# benjolin_1_6.net
KiCad netlist of a schematic drawn in EAGLE
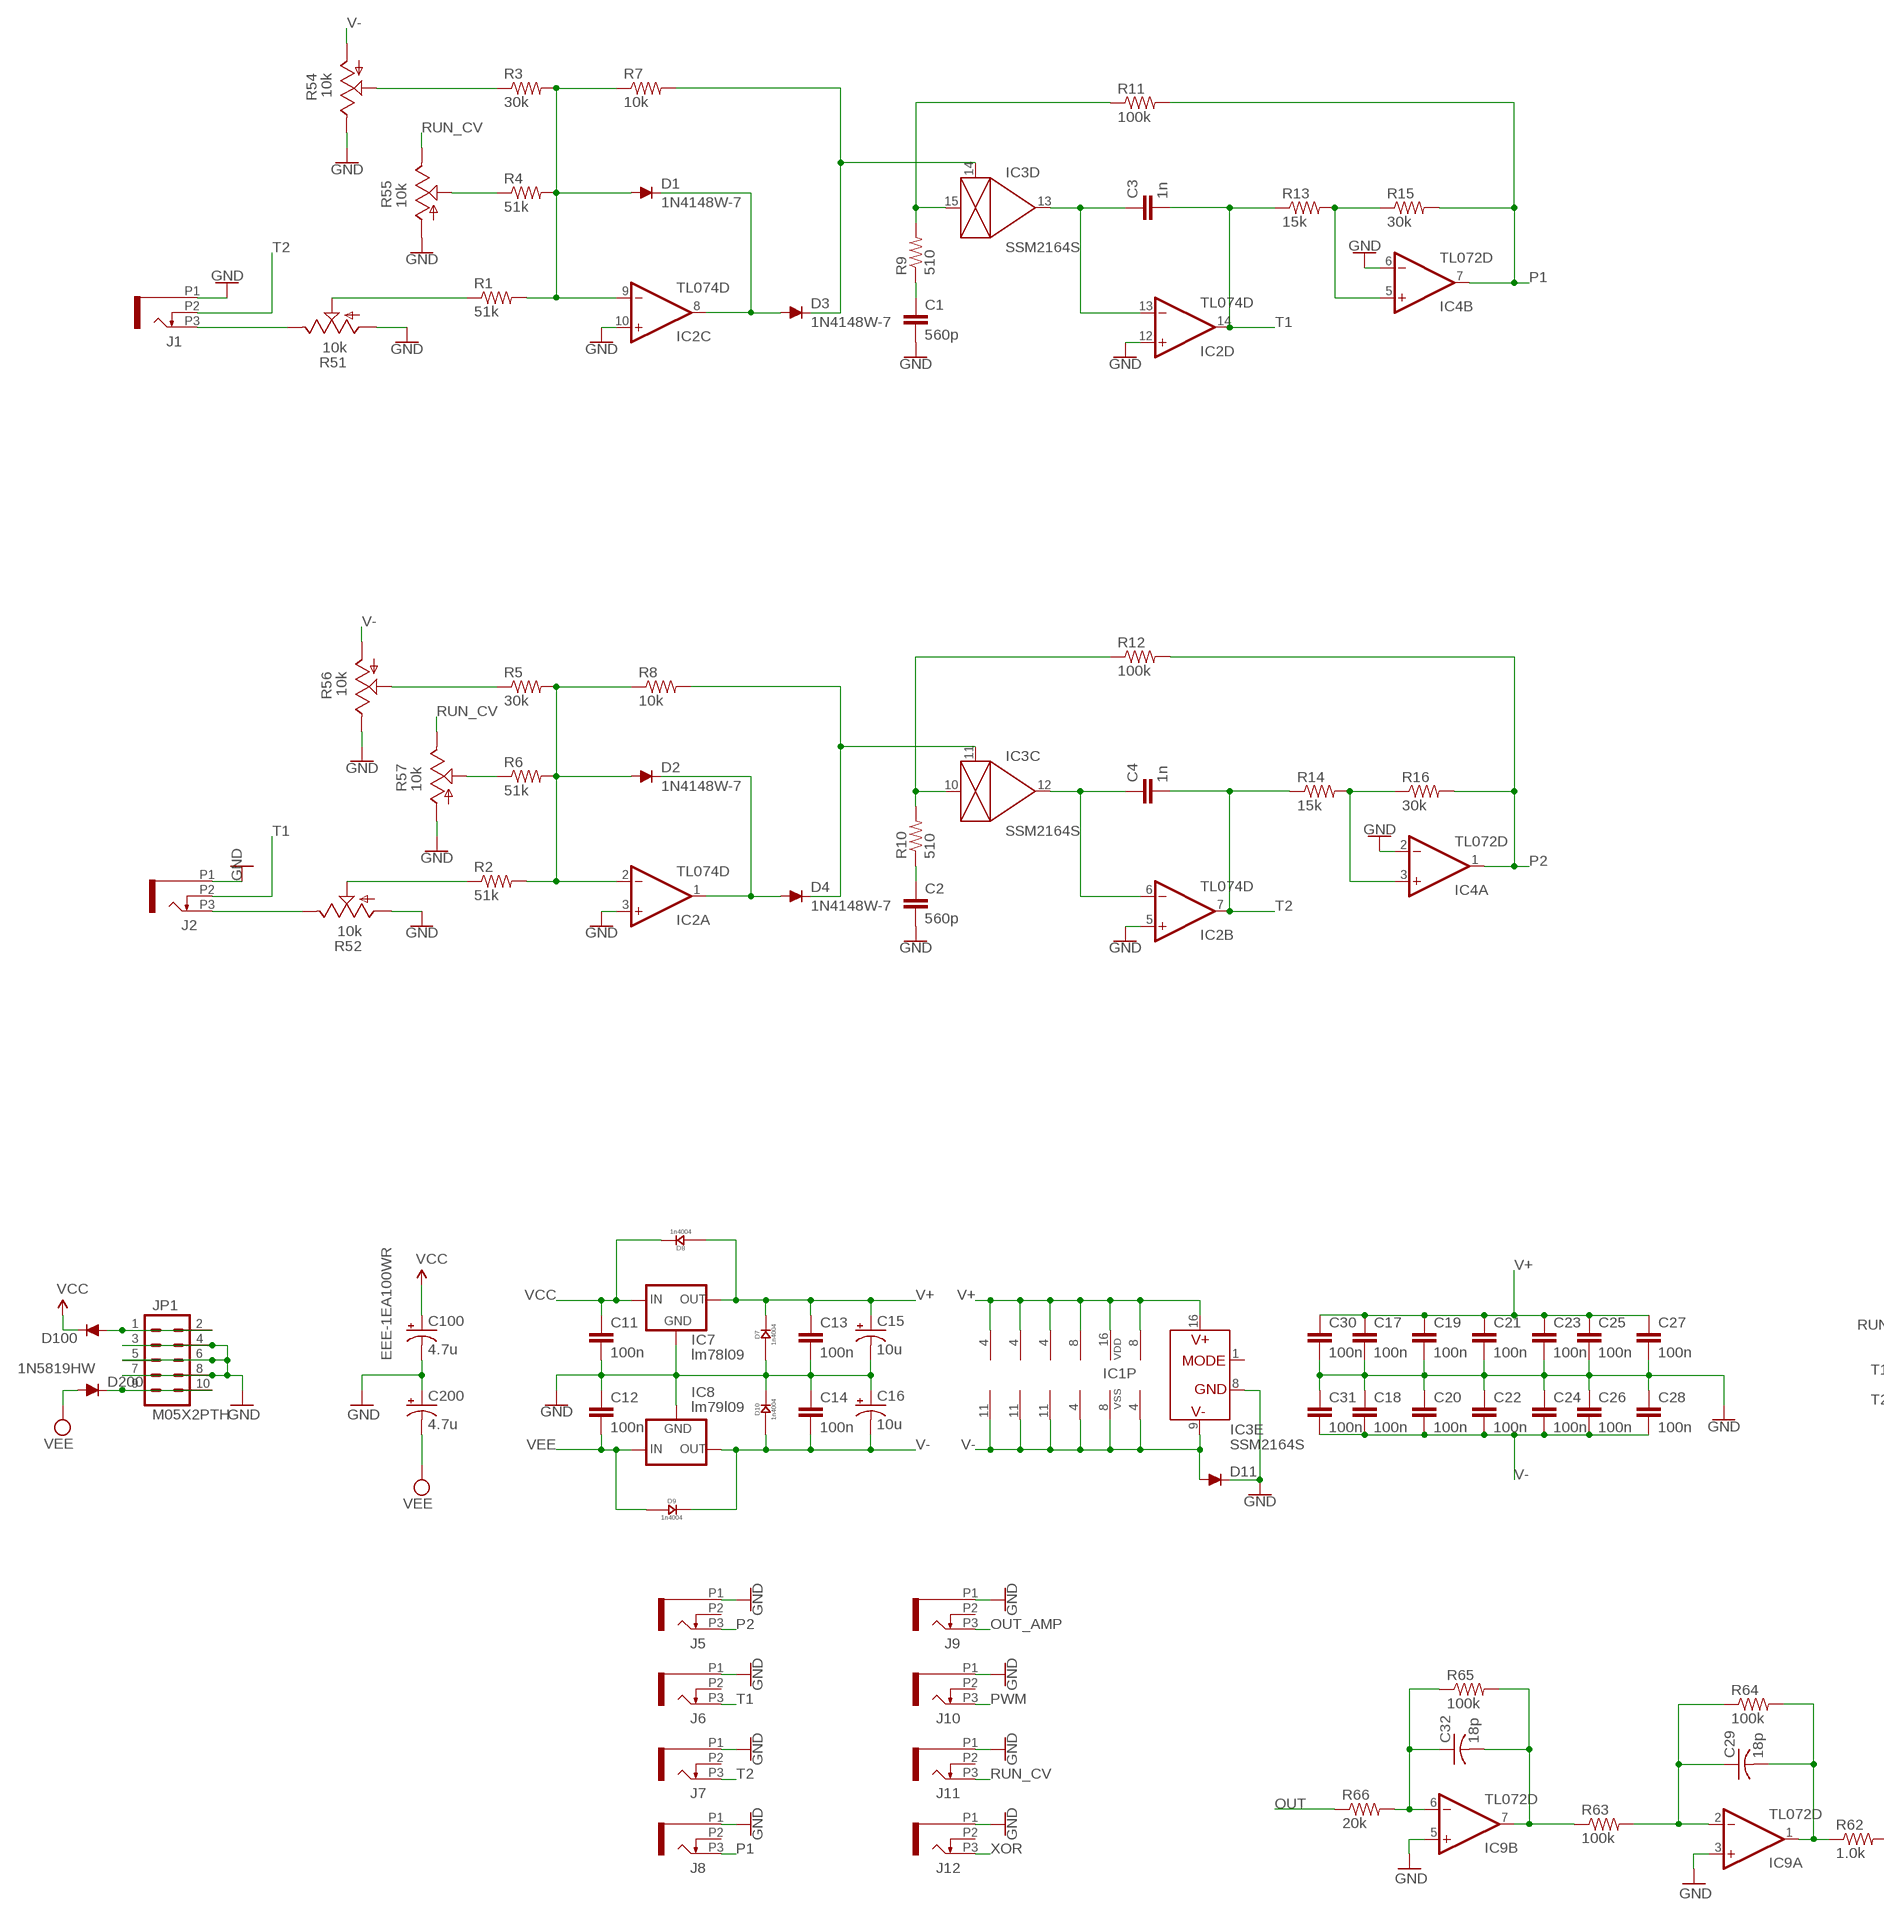
[diagram p0: schematic, sheet 1, part 1 of 2]
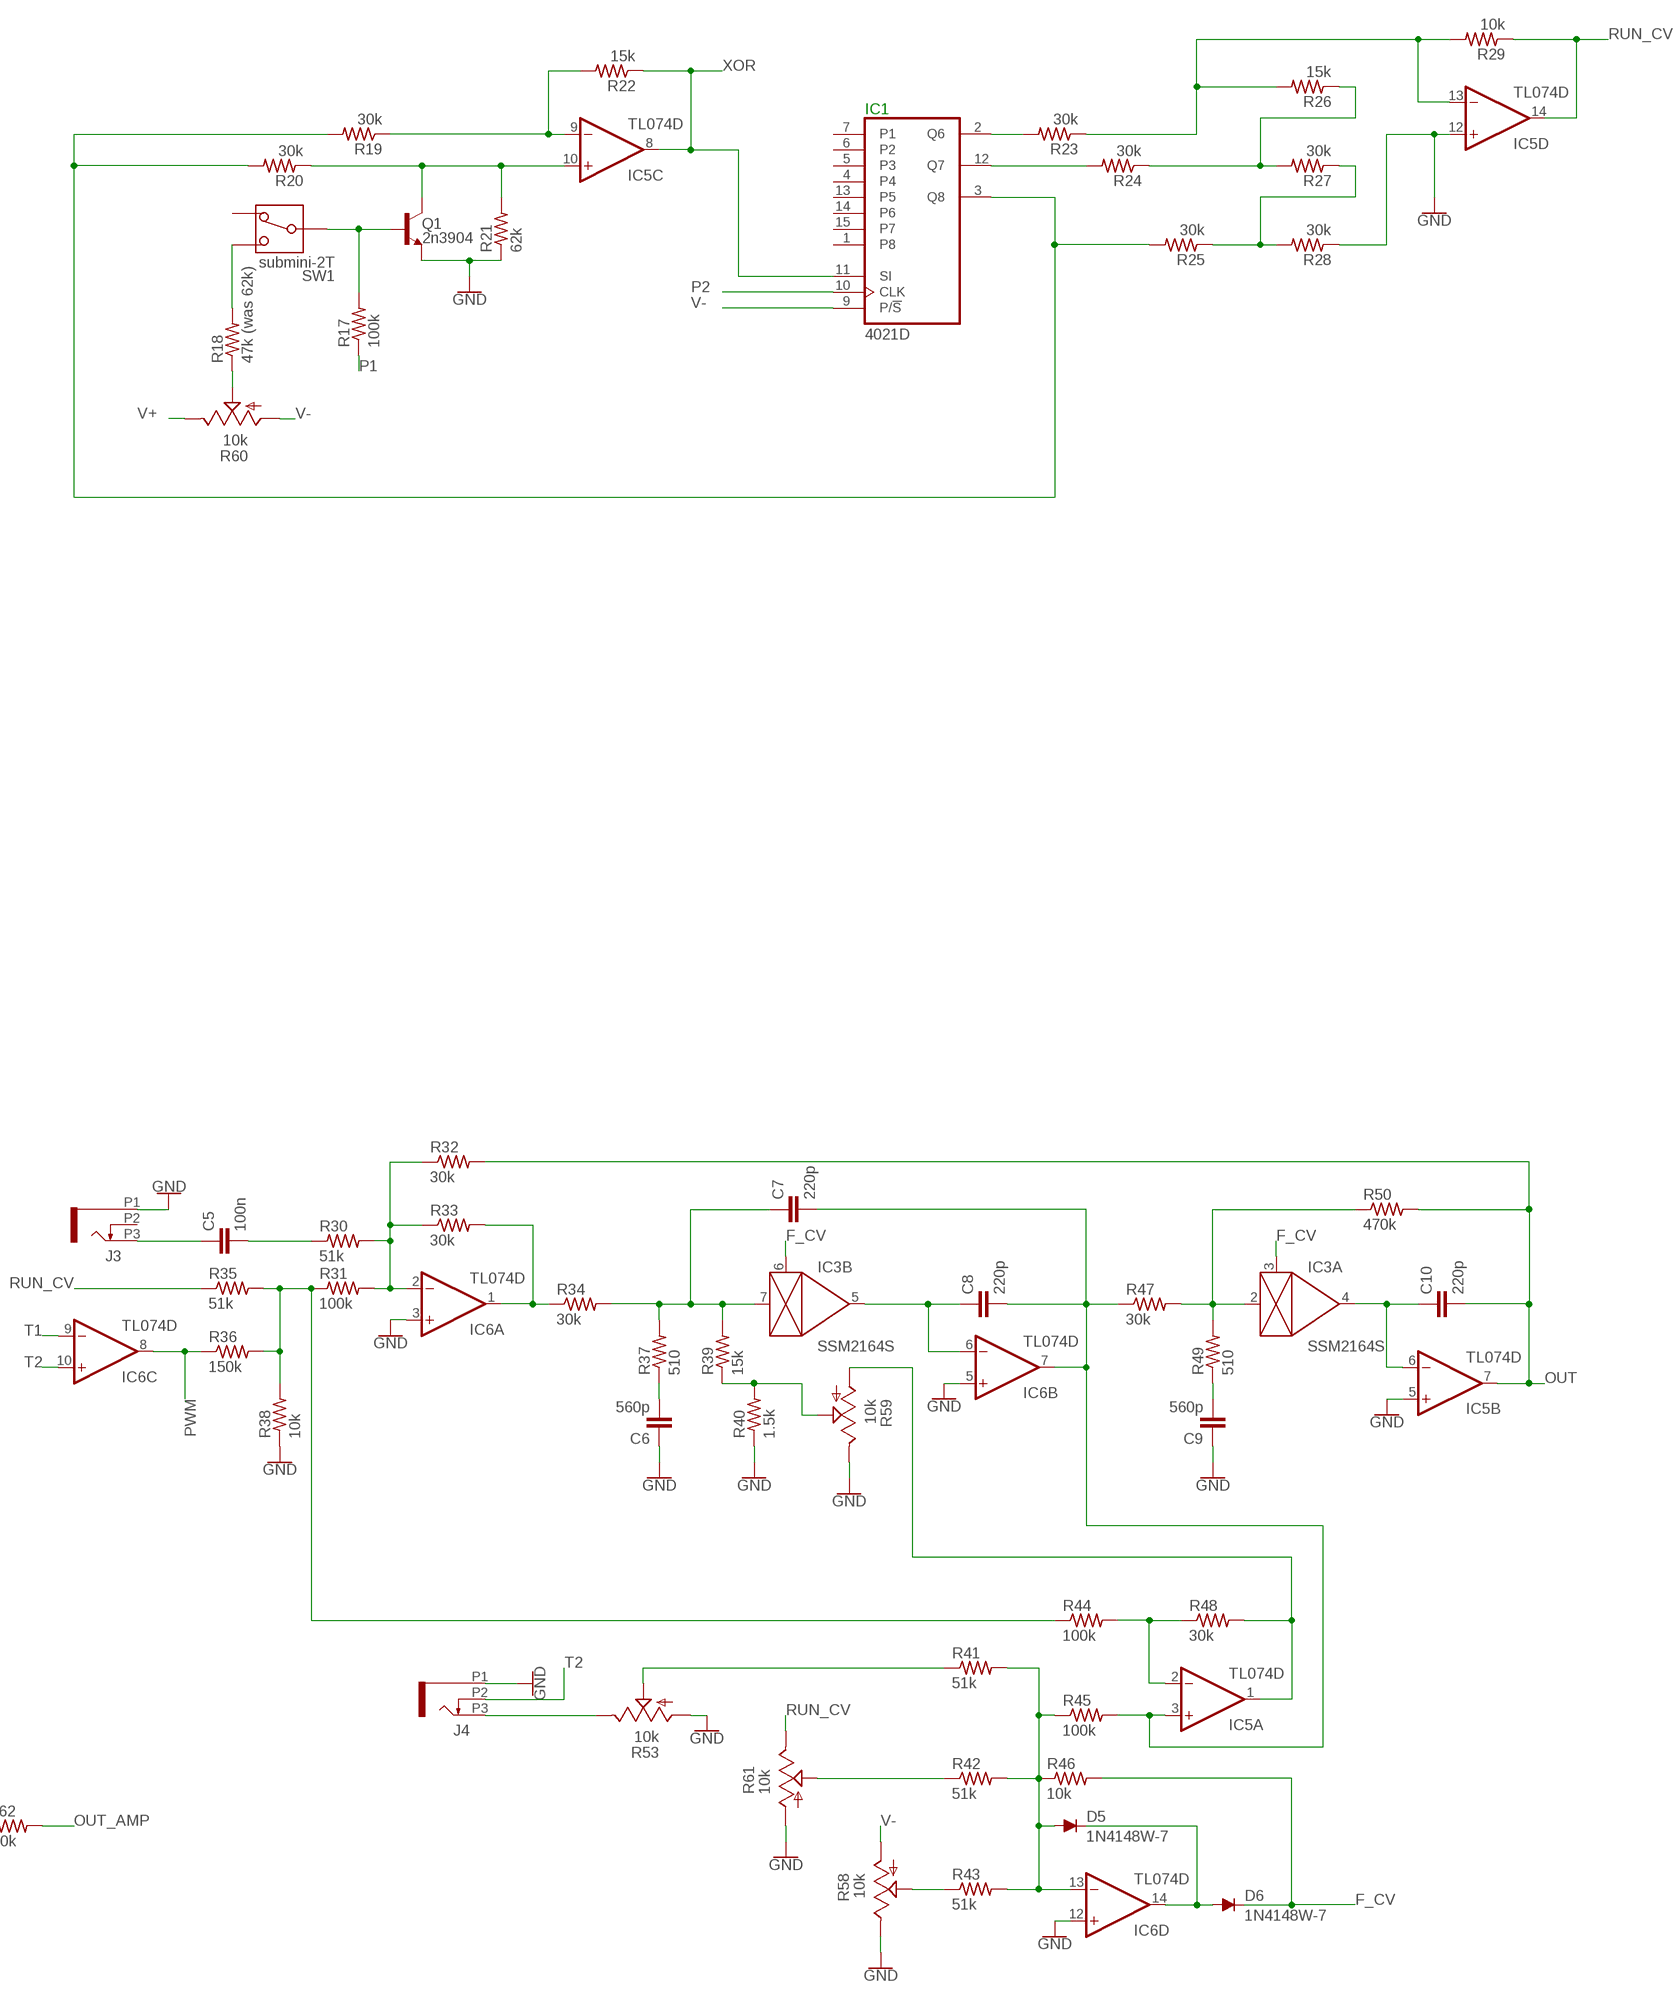
[diagram p1: schematic, sheet 1, part 2 of 2]

(export (version "E")
  (design (tool "Eeschema 10.0.6"))
  (components
    (comp (ref "C1")
      (value "560p")
      (footprint "eagle-import:C0603")
      (libsource (lib "eagle-import") (part "C-EUC0603"))
    )
    (comp (ref "C2")
      (value "560p")
      (footprint "eagle-import:C0603")
      (libsource (lib "eagle-import") (part "C-EUC0603"))
    )
    (comp (ref "C3")
      (value "1n")
      (footprint "eagle-import:C0603")
      (libsource (lib "eagle-import") (part "C-EUC0603"))
    )
    (comp (ref "C4")
      (value "1n")
      (footprint "eagle-import:C0603")
      (libsource (lib "eagle-import") (part "C-EUC0603"))
    )
    (comp (ref "C5")
      (value "100n")
      (footprint "eagle-import:C0603")
      (libsource (lib "eagle-import") (part "C-EUC0603"))
    )
    (comp (ref "C6")
      (value "560p")
      (footprint "eagle-import:C0603")
      (libsource (lib "eagle-import") (part "C-EUC0603"))
    )
    (comp (ref "C7")
      (value "220p")
      (footprint "eagle-import:C0603")
      (libsource (lib "eagle-import") (part "C-EUC0603"))
    )
    (comp (ref "C8")
      (value "220p")
      (footprint "eagle-import:C0603")
      (libsource (lib "eagle-import") (part "C-EUC0603"))
    )
    (comp (ref "C9")
      (value "560p")
      (footprint "eagle-import:C0603")
      (libsource (lib "eagle-import") (part "C-EUC0603"))
    )
    (comp (ref "C10")
      (value "220p")
      (footprint "eagle-import:C0603")
      (libsource (lib "eagle-import") (part "C-EUC0603"))
    )
    (comp (ref "C11")
      (value "100n")
      (footprint "eagle-import:C0603")
      (libsource (lib "eagle-import") (part "C-EUC0603"))
    )
    (comp (ref "C12")
      (value "100n")
      (footprint "eagle-import:C0603")
      (libsource (lib "eagle-import") (part "C-EUC0603"))
    )
    (comp (ref "C13")
      (value "100n")
      (footprint "eagle-import:C0603")
      (libsource (lib "eagle-import") (part "C-EUC0603"))
    )
    (comp (ref "C14")
      (value "100n")
      (footprint "eagle-import:C0603")
      (libsource (lib "eagle-import") (part "C-EUC0603"))
    )
    (comp (ref "C15")
      (value "10u")
      (footprint "eagle-import:PANASONIC_A")
      (libsource (lib "eagle-import") (part "CPOL-USA"))
    )
    (comp (ref "C16")
      (value "10u")
      (footprint "eagle-import:PANASONIC_A")
      (libsource (lib "eagle-import") (part "CPOL-USA"))
    )
    (comp (ref "C17")
      (value "100n")
      (footprint "eagle-import:C0603")
      (libsource (lib "eagle-import") (part "C-EUC0603"))
    )
    (comp (ref "C18")
      (value "100n")
      (footprint "eagle-import:C0603")
      (libsource (lib "eagle-import") (part "C-EUC0603"))
    )
    (comp (ref "C19")
      (value "100n")
      (footprint "eagle-import:C0603")
      (libsource (lib "eagle-import") (part "C-EUC0603"))
    )
    (comp (ref "C20")
      (value "100n")
      (footprint "eagle-import:C0603")
      (libsource (lib "eagle-import") (part "C-EUC0603"))
    )
    (comp (ref "C21")
      (value "100n")
      (footprint "eagle-import:C0603")
      (libsource (lib "eagle-import") (part "C-EUC0603"))
    )
    (comp (ref "C22")
      (value "100n")
      (footprint "eagle-import:C0603")
      (libsource (lib "eagle-import") (part "C-EUC0603"))
    )
    (comp (ref "C23")
      (value "100n")
      (footprint "eagle-import:C0603")
      (libsource (lib "eagle-import") (part "C-EUC0603"))
    )
    (comp (ref "C24")
      (value "100n")
      (footprint "eagle-import:C0603")
      (libsource (lib "eagle-import") (part "C-EUC0603"))
    )
    (comp (ref "C25")
      (value "100n")
      (footprint "eagle-import:C0603")
      (libsource (lib "eagle-import") (part "C-EUC0603"))
    )
    (comp (ref "C26")
      (value "100n")
      (footprint "eagle-import:C0603")
      (libsource (lib "eagle-import") (part "C-EUC0603"))
    )
    (comp (ref "C27")
      (value "100n")
      (footprint "eagle-import:C0603")
      (libsource (lib "eagle-import") (part "C-EUC0603"))
    )
    (comp (ref "C28")
      (value "100n")
      (footprint "eagle-import:C0603")
      (libsource (lib "eagle-import") (part "C-EUC0603"))
    )
    (comp (ref "C29")
      (value "18p")
      (footprint "eagle-import:C0603")
      (libsource (lib "eagle-import") (part "C-USC0603"))
    )
    (comp (ref "C30")
      (value "100n")
      (footprint "eagle-import:C0603")
      (libsource (lib "eagle-import") (part "C-EUC0603"))
    )
    (comp (ref "C31")
      (value "100n")
      (footprint "eagle-import:C0603")
      (libsource (lib "eagle-import") (part "C-EUC0603"))
    )
    (comp (ref "C32")
      (value "18p")
      (footprint "eagle-import:C0603")
      (libsource (lib "eagle-import") (part "C-USC0603"))
    )
    (comp (ref "C100")
      (value "4.7u")
      (footprint "eagle-import:PANASONIC_A")
      (libsource (lib "eagle-import") (part "CPOL-USA"))
    )
    (comp (ref "C200")
      (value "4.7u")
      (footprint "eagle-import:PANASONIC_A")
      (libsource (lib "eagle-import") (part "CPOL-USA"))
    )
    (comp (ref "D1")
      (value "1N4148W-7")
      (footprint "eagle-import:SOD123")
      (libsource (lib "eagle-import") (part "1N4148W-7"))
    )
    (comp (ref "D2")
      (value "1N4148W-7")
      (footprint "eagle-import:SOD123")
      (libsource (lib "eagle-import") (part "1N4148W-7"))
    )
    (comp (ref "D3")
      (value "1N4148W-7")
      (footprint "eagle-import:SOD123")
      (libsource (lib "eagle-import") (part "1N4148W-7"))
    )
    (comp (ref "D4")
      (value "1N4148W-7")
      (footprint "eagle-import:SOD123")
      (libsource (lib "eagle-import") (part "1N4148W-7"))
    )
    (comp (ref "D5")
      (value "1N4148W-7")
      (footprint "eagle-import:SOD123")
      (libsource (lib "eagle-import") (part "1N4148W-7"))
    )
    (comp (ref "D6")
      (value "1N4148W-7")
      (footprint "eagle-import:SOD123")
      (libsource (lib "eagle-import") (part "1N4148W-7"))
    )
    (comp (ref "D7")
      (value "1n4004")
      (footprint "eagle-import:DO-214AC")
      (libsource (lib "eagle-import") (part "D-SMA"))
    )
    (comp (ref "D8")
      (value "1n4004")
      (footprint "eagle-import:DO-214AC")
      (libsource (lib "eagle-import") (part "D-SMA"))
    )
    (comp (ref "D9")
      (value "1n4004")
      (footprint "eagle-import:DO-214AC")
      (libsource (lib "eagle-import") (part "D-SMA"))
    )
    (comp (ref "D10")
      (value "1n4004")
      (footprint "eagle-import:DO-214AC")
      (libsource (lib "eagle-import") (part "D-SMA"))
    )
    (comp (ref "D11")
      (value "1N5819HW")
      (footprint "eagle-import:SOD123")
      (libsource (lib "eagle-import") (part "DIODE-SOD123"))
    )
    (comp (ref "D100")
      (value "1N5819HW")
      (footprint "eagle-import:SOD123")
      (libsource (lib "eagle-import") (part "DIODE-SOD123"))
    )
    (comp (ref "D200")
      (value "1N5819HW")
      (footprint "eagle-import:SOD123")
      (libsource (lib "eagle-import") (part "DIODE-SOD123"))
    )
    (comp (ref "IC1")
      (value "4021D")
      (footprint "eagle-import:SO16")
      (libsource (lib "eagle-import") (part "4021D"))
    )
    (comp (ref "IC2")
      (value "TL074D")
      (footprint "eagle-import:SO14")
      (libsource (lib "eagle-import") (part "TL074D"))
    )
    (comp (ref "IC3")
      (value "SSM2164S")
      (footprint "eagle-import:SOIC16N")
      (libsource (lib "eagle-import") (part "SSM2164S"))
    )
    (comp (ref "IC4")
      (value "TL072D")
      (footprint "eagle-import:SO08")
      (libsource (lib "eagle-import") (part "TL072D"))
    )
    (comp (ref "IC5")
      (value "TL074D")
      (footprint "eagle-import:SO14")
      (libsource (lib "eagle-import") (part "TL074D"))
    )
    (comp (ref "IC6")
      (value "TL074D")
      (footprint "eagle-import:SO14")
      (libsource (lib "eagle-import") (part "TL074D"))
    )
    (comp (ref "IC7")
      (value "lm78l09")
      (footprint "eagle-import:78LXX")
      (libsource (lib "eagle-import") (part "78LXX"))
    )
    (comp (ref "IC8")
      (value "lm79l09")
      (footprint "eagle-import:79LXX")
      (libsource (lib "eagle-import") (part "79LXX"))
    )
    (comp (ref "IC9")
      (value "TL072D")
      (footprint "eagle-import:SO08")
      (libsource (lib "eagle-import") (part "TL072D"))
    )
    (comp (ref "J1")
      (value "PJ301_THONKICONN6")
      (footprint "eagle-import:WQP_PJ_301M6")
      (libsource (lib "eagle-import") (part "PJ301_THONKICONN6"))
    )
    (comp (ref "J2")
      (value "PJ301_THONKICONN6")
      (footprint "eagle-import:WQP_PJ_301M6")
      (libsource (lib "eagle-import") (part "PJ301_THONKICONN6"))
    )
    (comp (ref "J3")
      (value "PJ301_THONKICONN6")
      (footprint "eagle-import:WQP_PJ_301M6")
      (libsource (lib "eagle-import") (part "PJ301_THONKICONN6"))
    )
    (comp (ref "J4")
      (value "PJ301_THONKICONN6")
      (footprint "eagle-import:WQP_PJ_301M6")
      (libsource (lib "eagle-import") (part "PJ301_THONKICONN6"))
    )
    (comp (ref "J5")
      (value "PJ301_THONKICONN6")
      (footprint "eagle-import:WQP_PJ_301M6")
      (libsource (lib "eagle-import") (part "PJ301_THONKICONN6"))
    )
    (comp (ref "J6")
      (value "PJ301_THONKICONN6")
      (footprint "eagle-import:WQP_PJ_301M6")
      (libsource (lib "eagle-import") (part "PJ301_THONKICONN6"))
    )
    (comp (ref "J7")
      (value "PJ301_THONKICONN6")
      (footprint "eagle-import:WQP_PJ_301M6")
      (libsource (lib "eagle-import") (part "PJ301_THONKICONN6"))
    )
    (comp (ref "J8")
      (value "PJ301_THONKICONN6")
      (footprint "eagle-import:WQP_PJ_301M6")
      (libsource (lib "eagle-import") (part "PJ301_THONKICONN6"))
    )
    (comp (ref "J9")
      (value "PJ301_THONKICONN6")
      (footprint "eagle-import:WQP_PJ_301M6")
      (libsource (lib "eagle-import") (part "PJ301_THONKICONN6"))
    )
    (comp (ref "J10")
      (value "PJ301_THONKICONN6")
      (footprint "eagle-import:WQP_PJ_301M6")
      (libsource (lib "eagle-import") (part "PJ301_THONKICONN6"))
    )
    (comp (ref "J11")
      (value "PJ301_THONKICONN6")
      (footprint "eagle-import:WQP_PJ_301M6")
      (libsource (lib "eagle-import") (part "PJ301_THONKICONN6"))
    )
    (comp (ref "J12")
      (value "PJ301_THONKICONN6")
      (footprint "eagle-import:WQP_PJ_301M6")
      (libsource (lib "eagle-import") (part "PJ301_THONKICONN6"))
    )
    (comp (ref "JP1")
      (value "M05X2PTH")
      (footprint "eagle-import:AVR_ICSP")
      (libsource (lib "eagle-import") (part "M05X2PTH"))
    )
    (comp (ref "Q1")
      (value "2n3904")
      (footprint "eagle-import:SOT23-3")
      (libsource (lib "eagle-import") (part "TRANS_NPN-MMBT2222AL"))
    )
    (comp (ref "R1")
      (value "51k")
      (footprint "eagle-import:R0603")
      (libsource (lib "eagle-import") (part "resistor_348_R-US_R0603"))
    )
    (comp (ref "R2")
      (value "51k")
      (footprint "eagle-import:R0603")
      (libsource (lib "eagle-import") (part "resistor_348_R-US_R0603"))
    )
    (comp (ref "R3")
      (value "30k")
      (footprint "eagle-import:R0603")
      (libsource (lib "eagle-import") (part "resistor_348_R-US_R0603"))
    )
    (comp (ref "R4")
      (value "51k")
      (footprint "eagle-import:R0603")
      (libsource (lib "eagle-import") (part "resistor_348_R-US_R0603"))
    )
    (comp (ref "R5")
      (value "30k")
      (footprint "eagle-import:R0603")
      (libsource (lib "eagle-import") (part "resistor_348_R-US_R0603"))
    )
    (comp (ref "R6")
      (value "51k")
      (footprint "eagle-import:R0603")
      (libsource (lib "eagle-import") (part "resistor_348_R-US_R0603"))
    )
    (comp (ref "R7")
      (value "10k")
      (footprint "eagle-import:R0603")
      (libsource (lib "eagle-import") (part "resistor_348_R-US_R0603"))
    )
    (comp (ref "R8")
      (value "10k")
      (footprint "eagle-import:R0603")
      (libsource (lib "eagle-import") (part "resistor_348_R-US_R0603"))
    )
    (comp (ref "R9")
      (value "510")
      (footprint "eagle-import:R0603")
      (libsource (lib "eagle-import") (part "resistor_348_R-US_R0603"))
    )
    (comp (ref "R10")
      (value "510")
      (footprint "eagle-import:R0603")
      (libsource (lib "eagle-import") (part "resistor_348_R-US_R0603"))
    )
    (comp (ref "R11")
      (value "100k")
      (footprint "eagle-import:R0603")
      (libsource (lib "eagle-import") (part "resistor_348_R-US_R0603"))
    )
    (comp (ref "R12")
      (value "100k")
      (footprint "eagle-import:R0603")
      (libsource (lib "eagle-import") (part "resistor_348_R-US_R0603"))
    )
    (comp (ref "R13")
      (value "15k")
      (footprint "eagle-import:R0603")
      (libsource (lib "eagle-import") (part "resistor_348_R-US_R0603"))
    )
    (comp (ref "R14")
      (value "15k")
      (footprint "eagle-import:R0603")
      (libsource (lib "eagle-import") (part "resistor_348_R-US_R0603"))
    )
    (comp (ref "R15")
      (value "30k")
      (footprint "eagle-import:R0603")
      (libsource (lib "eagle-import") (part "resistor_348_R-US_R0603"))
    )
    (comp (ref "R16")
      (value "30k")
      (footprint "eagle-import:R0603")
      (libsource (lib "eagle-import") (part "resistor_348_R-US_R0603"))
    )
    (comp (ref "R17")
      (value "100k")
      (footprint "eagle-import:R0603")
      (libsource (lib "eagle-import") (part "resistor_348_R-US_R0603"))
    )
    (comp (ref "R18")
      (value "47k (was 62k)")
      (footprint "eagle-import:R0603")
      (libsource (lib "eagle-import") (part "resistor_348_R-US_R0603"))
    )
    (comp (ref "R19")
      (value "30k")
      (footprint "eagle-import:R0603")
      (libsource (lib "eagle-import") (part "resistor_348_R-US_R0603"))
    )
    (comp (ref "R20")
      (value "30k")
      (footprint "eagle-import:R0603")
      (libsource (lib "eagle-import") (part "resistor_348_R-US_R0603"))
    )
    (comp (ref "R21")
      (value "62k")
      (footprint "eagle-import:R0603")
      (libsource (lib "eagle-import") (part "resistor_348_R-US_R0603"))
    )
    (comp (ref "R22")
      (value "15k")
      (footprint "eagle-import:R0603")
      (libsource (lib "eagle-import") (part "resistor_348_R-US_R0603"))
    )
    (comp (ref "R23")
      (value "30k")
      (footprint "eagle-import:R0603")
      (libsource (lib "eagle-import") (part "resistor_348_R-US_R0603"))
    )
    (comp (ref "R24")
      (value "30k")
      (footprint "eagle-import:R0603")
      (libsource (lib "eagle-import") (part "resistor_348_R-US_R0603"))
    )
    (comp (ref "R25")
      (value "30k")
      (footprint "eagle-import:R0603")
      (libsource (lib "eagle-import") (part "resistor_348_R-US_R0603"))
    )
    (comp (ref "R26")
      (value "15k")
      (footprint "eagle-import:R0603")
      (libsource (lib "eagle-import") (part "resistor_348_R-US_R0603"))
    )
    (comp (ref "R27")
      (value "30k")
      (footprint "eagle-import:R0603")
      (libsource (lib "eagle-import") (part "resistor_348_R-US_R0603"))
    )
    (comp (ref "R28")
      (value "30k")
      (footprint "eagle-import:R0603")
      (libsource (lib "eagle-import") (part "resistor_348_R-US_R0603"))
    )
    (comp (ref "R29")
      (value "10k")
      (footprint "eagle-import:R0603")
      (libsource (lib "eagle-import") (part "resistor_348_R-US_R0603"))
    )
    (comp (ref "R30")
      (value "51k")
      (footprint "eagle-import:R0603")
      (libsource (lib "eagle-import") (part "resistor_348_R-US_R0603"))
    )
    (comp (ref "R31")
      (value "100k")
      (footprint "eagle-import:R0603")
      (libsource (lib "eagle-import") (part "resistor_348_R-US_R0603"))
    )
    (comp (ref "R32")
      (value "30k")
      (footprint "eagle-import:R0603")
      (libsource (lib "eagle-import") (part "resistor_348_R-US_R0603"))
    )
    (comp (ref "R33")
      (value "30k")
      (footprint "eagle-import:R0603")
      (libsource (lib "eagle-import") (part "resistor_348_R-US_R0603"))
    )
    (comp (ref "R34")
      (value "30k")
      (footprint "eagle-import:R0603")
      (libsource (lib "eagle-import") (part "resistor_348_R-US_R0603"))
    )
    (comp (ref "R35")
      (value "51k")
      (footprint "eagle-import:R0603")
      (libsource (lib "eagle-import") (part "resistor_348_R-US_R0603"))
    )
    (comp (ref "R36")
      (value "150k")
      (footprint "eagle-import:R0603")
      (libsource (lib "eagle-import") (part "resistor_348_R-US_R0603"))
    )
    (comp (ref "R37")
      (value "510")
      (footprint "eagle-import:R0603")
      (libsource (lib "eagle-import") (part "resistor_348_R-US_R0603"))
    )
    (comp (ref "R38")
      (value "10k")
      (footprint "eagle-import:R0603")
      (libsource (lib "eagle-import") (part "resistor_348_R-US_R0603"))
    )
    (comp (ref "R39")
      (value "15k")
      (footprint "eagle-import:R0603")
      (libsource (lib "eagle-import") (part "resistor_348_R-US_R0603"))
    )
    (comp (ref "R40")
      (value "1.5k")
      (footprint "eagle-import:R0603")
      (libsource (lib "eagle-import") (part "resistor_348_R-US_R0603"))
    )
    (comp (ref "R41")
      (value "51k")
      (footprint "eagle-import:R0603")
      (libsource (lib "eagle-import") (part "resistor_348_R-US_R0603"))
    )
    (comp (ref "R42")
      (value "51k")
      (footprint "eagle-import:R0603")
      (libsource (lib "eagle-import") (part "resistor_348_R-US_R0603"))
    )
    (comp (ref "R43")
      (value "51k")
      (footprint "eagle-import:R0603")
      (libsource (lib "eagle-import") (part "resistor_348_R-US_R0603"))
    )
    (comp (ref "R44")
      (value "100k")
      (footprint "eagle-import:R0603")
      (libsource (lib "eagle-import") (part "resistor_348_R-US_R0603"))
    )
    (comp (ref "R45")
      (value "100k")
      (footprint "eagle-import:R0603")
      (libsource (lib "eagle-import") (part "resistor_348_R-US_R0603"))
    )
    (comp (ref "R46")
      (value "10k")
      (footprint "eagle-import:R0603")
      (libsource (lib "eagle-import") (part "resistor_348_R-US_R0603"))
    )
    (comp (ref "R47")
      (value "30k")
      (footprint "eagle-import:R0603")
      (libsource (lib "eagle-import") (part "resistor_348_R-US_R0603"))
    )
    (comp (ref "R48")
      (value "30k")
      (footprint "eagle-import:R0603")
      (libsource (lib "eagle-import") (part "resistor_348_R-US_R0603"))
    )
    (comp (ref "R49")
      (value "510")
      (footprint "eagle-import:R0603")
      (libsource (lib "eagle-import") (part "resistor_348_R-US_R0603"))
    )
    (comp (ref "R50")
      (value "470k")
      (footprint "eagle-import:R0603")
      (libsource (lib "eagle-import") (part "resistor_348_R-US_R0603"))
    )
    (comp (ref "R51")
      (value "10k")
      (footprint "eagle-import:ALPS_POT_NARROW")
      (libsource (lib "eagle-import") (part "POT_USVERTICAL_NARROW"))
    )
    (comp (ref "R52")
      (value "10k")
      (footprint "eagle-import:ALPS_POT_NARROW")
      (libsource (lib "eagle-import") (part "POT_USVERTICAL_NARROW"))
    )
    (comp (ref "R53")
      (value "10k")
      (footprint "eagle-import:ALPS_POT_NARROW")
      (libsource (lib "eagle-import") (part "POT_USVERTICAL_NARROW"))
    )
    (comp (ref "R54")
      (value "10k")
      (footprint "eagle-import:ALPS_POT_VERTICAL_PS")
      (libsource (lib "eagle-import") (part "POT_USVERTICAL_PS"))
    )
    (comp (ref "R55")
      (value "10k")
      (footprint "eagle-import:ALPS_POT_VERTICAL_PS")
      (libsource (lib "eagle-import") (part "POT_USVERTICAL_PS"))
    )
    (comp (ref "R56")
      (value "10k")
      (footprint "eagle-import:ALPS_POT_VERTICAL_PS")
      (libsource (lib "eagle-import") (part "POT_USVERTICAL_PS"))
    )
    (comp (ref "R57")
      (value "10k")
      (footprint "eagle-import:ALPS_POT_VERTICAL_PS")
      (libsource (lib "eagle-import") (part "POT_USVERTICAL_PS"))
    )
    (comp (ref "R58")
      (value "10k")
      (footprint "eagle-import:ALPS_POT_VERTICAL_PS")
      (libsource (lib "eagle-import") (part "POT_USVERTICAL_PS"))
    )
    (comp (ref "R59")
      (value "10k")
      (footprint "eagle-import:ALPS_POT_VERTICAL_PS")
      (libsource (lib "eagle-import") (part "POT_USVERTICAL_PS"))
    )
    (comp (ref "R60")
      (value "10k")
      (footprint "eagle-import:ALPS_POT_VERTICAL_PS")
      (libsource (lib "eagle-import") (part "POT_USVERTICAL_PS"))
    )
    (comp (ref "R61")
      (value "10k")
      (footprint "eagle-import:ALPS_POT_VERTICAL_PS")
      (libsource (lib "eagle-import") (part "POT_USVERTICAL_PS"))
    )
    (comp (ref "R62")
      (value "1.0k")
      (footprint "eagle-import:R0603")
      (libsource (lib "eagle-import") (part "R-US_R0603"))
    )
    (comp (ref "R63")
      (value "100k")
      (footprint "eagle-import:R0603")
      (libsource (lib "eagle-import") (part "R-US_R0603"))
    )
    (comp (ref "R64")
      (value "100k")
      (footprint "eagle-import:R0603")
      (libsource (lib "eagle-import") (part "R-US_R0603"))
    )
    (comp (ref "R65")
      (value "100k")
      (footprint "eagle-import:R0603")
      (libsource (lib "eagle-import") (part "R-US_R0603"))
    )
    (comp (ref "R66")
      (value "20k")
      (footprint "eagle-import:R0603")
      (libsource (lib "eagle-import") (part "R-US_R0603"))
    )
    (comp (ref "SW1")
      (value "submini-2T")
      (footprint "eagle-import:SPDT-SUB")
      (libsource (lib "eagle-import") (part "SPDTT"))
    )
  )
  (nets
    (net (code "1") (name "F_CV") (class "Default")
      (node (ref "D6") (pin "C") (pinfunction "C_C") (pintype "passive"))
      (node (ref "IC3") (pin "3") (pinfunction "CTRL_3") (pintype "input"))
      (node (ref "IC3") (pin "6") (pinfunction "CTRL_6") (pintype "input"))
      (node (ref "R46") (pin "2") (pinfunction "2_2") (pintype "passive"))
    )
    (net (code "2") (name "GND") (class "Default")
      (node (ref "C1") (pin "2") (pinfunction "2_2") (pintype "passive"))
      (node (ref "C100") (pin "-") (pinfunction "-_-") (pintype "passive"))
      (node (ref "C11") (pin "2") (pinfunction "2_2") (pintype "passive"))
      (node (ref "C12") (pin "1") (pinfunction "1_1") (pintype "passive"))
      (node (ref "C13") (pin "2") (pinfunction "2_2") (pintype "passive"))
      (node (ref "C14") (pin "1") (pinfunction "1_1") (pintype "passive"))
      (node (ref "C15") (pin "-") (pinfunction "-_-") (pintype "passive"))
      (node (ref "C16") (pin "+") (pinfunction "+_+") (pintype "passive"))
      (node (ref "C17") (pin "2") (pinfunction "2_2") (pintype "passive"))
      (node (ref "C18") (pin "1") (pinfunction "1_1") (pintype "passive"))
      (node (ref "C19") (pin "2") (pinfunction "2_2") (pintype "passive"))
      (node (ref "C2") (pin "2") (pinfunction "2_2") (pintype "passive"))
      (node (ref "C20") (pin "1") (pinfunction "1_1") (pintype "passive"))
      (node (ref "C200") (pin "+") (pinfunction "+_+") (pintype "passive"))
      (node (ref "C21") (pin "2") (pinfunction "2_2") (pintype "passive"))
      (node (ref "C22") (pin "1") (pinfunction "1_1") (pintype "passive"))
      (node (ref "C23") (pin "2") (pinfunction "2_2") (pintype "passive"))
      (node (ref "C24") (pin "1") (pinfunction "1_1") (pintype "passive"))
      (node (ref "C25") (pin "2") (pinfunction "2_2") (pintype "passive"))
      (node (ref "C26") (pin "1") (pinfunction "1_1") (pintype "passive"))
      (node (ref "C27") (pin "2") (pinfunction "2_2") (pintype "passive"))
      (node (ref "C28") (pin "1") (pinfunction "1_1") (pintype "passive"))
      (node (ref "C30") (pin "2") (pinfunction "2_2") (pintype "passive"))
      (node (ref "C31") (pin "1") (pinfunction "1_1") (pintype "passive"))
      (node (ref "C6") (pin "1") (pinfunction "1_1") (pintype "passive"))
      (node (ref "C9") (pin "1") (pinfunction "1_1") (pintype "passive"))
      (node (ref "D10") (pin "2") (pinfunction "-_2") (pintype "passive"))
      (node (ref "D11") (pin "C") (pinfunction "C_C") (pintype "passive"))
      (node (ref "D7") (pin "1") (pinfunction "+_1") (pintype "passive"))
      (node (ref "IC2") (pin "10") (pinfunction "+IN_10") (pintype "input"))
      (node (ref "IC2") (pin "12") (pinfunction "+IN_12") (pintype "input"))
      (node (ref "IC2") (pin "3") (pinfunction "+IN_3") (pintype "input"))
      (node (ref "IC2") (pin "5") (pinfunction "+IN_5") (pintype "input"))
      (node (ref "IC3") (pin "8") (pinfunction "GND_8") (pintype "power_in"))
      (node (ref "IC4") (pin "2") (pinfunction "-IN_2") (pintype "input"))
      (node (ref "IC4") (pin "6") (pinfunction "-IN_6") (pintype "input"))
      (node (ref "IC5") (pin "12") (pinfunction "+IN_12") (pintype "input"))
      (node (ref "IC5") (pin "5") (pinfunction "+IN_5") (pintype "input"))
      (node (ref "IC6") (pin "12") (pinfunction "+IN_12") (pintype "input"))
      (node (ref "IC6") (pin "3") (pinfunction "+IN_3") (pintype "input"))
      (node (ref "IC6") (pin "5") (pinfunction "+IN_5") (pintype "input"))
      (node (ref "IC7") (pin "GND") (pinfunction "GND_GND") (pintype "input"))
      (node (ref "IC8") (pin "GND") (pinfunction "GND_GND") (pintype "input"))
      (node (ref "IC9") (pin "3") (pinfunction "+IN_3") (pintype "input"))
      (node (ref "IC9") (pin "5") (pinfunction "+IN_5") (pintype "input"))
      (node (ref "J1") (pin "P1") (pinfunction "1_P1") (pintype "passive"))
      (node (ref "J10") (pin "P1") (pinfunction "1_P1") (pintype "passive"))
      (node (ref "J11") (pin "P1") (pinfunction "1_P1") (pintype "passive"))
      (node (ref "J12") (pin "P1") (pinfunction "1_P1") (pintype "passive"))
      (node (ref "J2") (pin "P1") (pinfunction "1_P1") (pintype "passive"))
      (node (ref "J3") (pin "P1") (pinfunction "1_P1") (pintype "passive"))
      (node (ref "J4") (pin "P1") (pinfunction "1_P1") (pintype "passive"))
      (node (ref "J5") (pin "P1") (pinfunction "1_P1") (pintype "passive"))
      (node (ref "J6") (pin "P1") (pinfunction "1_P1") (pintype "passive"))
      (node (ref "J7") (pin "P1") (pinfunction "1_P1") (pintype "passive"))
      (node (ref "J8") (pin "P1") (pinfunction "1_P1") (pintype "passive"))
      (node (ref "J9") (pin "P1") (pinfunction "1_P1") (pintype "passive"))
      (node (ref "JP1") (pin "3") (pinfunction "3_3") (pintype "passive"))
      (node (ref "JP1") (pin "4") (pinfunction "4_4") (pintype "passive"))
      (node (ref "JP1") (pin "5") (pinfunction "5_5") (pintype "passive"))
      (node (ref "JP1") (pin "6") (pinfunction "6_6") (pintype "passive"))
      (node (ref "JP1") (pin "7") (pinfunction "7_7") (pintype "passive"))
      (node (ref "JP1") (pin "8") (pinfunction "8_8") (pintype "passive"))
      (node (ref "Q1") (pin "2") (pinfunction "E_2") (pintype "passive"))
      (node (ref "R21") (pin "1") (pinfunction "1_1") (pintype "passive"))
      (node (ref "R28") (pin "1") (pinfunction "1_1") (pintype "passive"))
      (node (ref "R38") (pin "1") (pinfunction "1_1") (pintype "passive"))
      (node (ref "R40") (pin "1") (pinfunction "1_1") (pintype "passive"))
      (node (ref "R51") (pin "P$3") (pinfunction "A_P$3") (pintype "passive"))
      (node (ref "R52") (pin "P$3") (pinfunction "A_P$3") (pintype "passive"))
      (node (ref "R53") (pin "P$3") (pinfunction "A_P$3") (pintype "passive"))
      (node (ref "R54") (pin "P$1") (pinfunction "E_P$1") (pintype "passive"))
      (node (ref "R55") (pin "P$3") (pinfunction "A_P$3") (pintype "passive"))
      (node (ref "R56") (pin "P$1") (pinfunction "E_P$1") (pintype "passive"))
      (node (ref "R57") (pin "P$3") (pinfunction "A_P$3") (pintype "passive"))
      (node (ref "R58") (pin "P$1") (pinfunction "E_P$1") (pintype "passive"))
      (node (ref "R59") (pin "P$1") (pinfunction "E_P$1") (pintype "passive"))
      (node (ref "R61") (pin "P$3") (pinfunction "A_P$3") (pintype "passive"))
    )
    (net (code "3") (name "Net-(C1-Pad1)") (class "Default")
      (node (ref "C1") (pin "1") (pinfunction "1_1") (pintype "passive"))
      (node (ref "R9") (pin "1") (pinfunction "1_1") (pintype "passive"))
    )
    (net (code "4") (name "Net-(C2-Pad1)") (class "Default")
      (node (ref "C2") (pin "1") (pinfunction "1_1") (pintype "passive"))
      (node (ref "R10") (pin "1") (pinfunction "1_1") (pintype "passive"))
    )
    (net (code "5") (name "Net-(C5-Pad2)") (class "Default")
      (node (ref "C5") (pin "2") (pinfunction "2_2") (pintype "passive"))
      (node (ref "R30") (pin "1") (pinfunction "1_1") (pintype "passive"))
    )
    (net (code "6") (name "Net-(C6-Pad2)") (class "Default")
      (node (ref "C6") (pin "2") (pinfunction "2_2") (pintype "passive"))
      (node (ref "R37") (pin "1") (pinfunction "1_1") (pintype "passive"))
    )
    (net (code "7") (name "Net-(C9-Pad2)") (class "Default")
      (node (ref "C9") (pin "2") (pinfunction "2_2") (pintype "passive"))
      (node (ref "R49") (pin "1") (pinfunction "1_1") (pintype "passive"))
    )
    (net (code "8") (name "Net-(D100-PadA)") (class "Default")
      (node (ref "D100") (pin "A") (pinfunction "A_A") (pintype "passive"))
      (node (ref "JP1") (pin "1") (pinfunction "1_1") (pintype "passive"))
      (node (ref "JP1") (pin "2") (pinfunction "2_2") (pintype "passive"))
    )
    (net (code "9") (name "Net-(D200-PadC)") (class "Default")
      (node (ref "D200") (pin "C") (pinfunction "C_C") (pintype "passive"))
      (node (ref "JP1") (pin "10") (pinfunction "10_10") (pintype "passive"))
      (node (ref "JP1") (pin "9") (pinfunction "9_9") (pintype "passive"))
    )
    (net (code "10") (name "Net-(IC1A-Q6)") (class "Default")
      (node (ref "IC1") (pin "2") (pinfunction "Q6_2") (pintype "output"))
      (node (ref "R23") (pin "2") (pinfunction "2_2") (pintype "passive"))
    )
    (net (code "11") (name "Net-(IC1A-Q7)") (class "Default")
      (node (ref "IC1") (pin "12") (pinfunction "Q7_12") (pintype "output"))
      (node (ref "R24") (pin "2") (pinfunction "2_2") (pintype "passive"))
    )
    (net (code "12") (name "Net-(IC1A-Q8)") (class "Default")
      (node (ref "IC1") (pin "3") (pinfunction "Q8_3") (pintype "output"))
      (node (ref "R19") (pin "2") (pinfunction "2_2") (pintype "passive"))
      (node (ref "R20") (pin "2") (pinfunction "2_2") (pintype "passive"))
      (node (ref "R25") (pin "2") (pinfunction "2_2") (pintype "passive"))
    )
    (net (code "13") (name "Net-(IC2A--IN)") (class "Default")
      (node (ref "D2") (pin "A") (pinfunction "A_A") (pintype "passive"))
      (node (ref "IC2") (pin "2") (pinfunction "-IN_2") (pintype "input"))
      (node (ref "R2") (pin "2") (pinfunction "2_2") (pintype "passive"))
      (node (ref "R5") (pin "2") (pinfunction "2_2") (pintype "passive"))
      (node (ref "R6") (pin "2") (pinfunction "2_2") (pintype "passive"))
      (node (ref "R8") (pin "1") (pinfunction "1_1") (pintype "passive"))
    )
    (net (code "14") (name "Net-(IC2A-OUT)") (class "Default")
      (node (ref "D2") (pin "C") (pinfunction "C_C") (pintype "passive"))
      (node (ref "D4") (pin "A") (pinfunction "A_A") (pintype "passive"))
      (node (ref "IC2") (pin "1") (pinfunction "OUT_1") (pintype "output"))
    )
    (net (code "15") (name "Net-(IC2B--IN)") (class "Default")
      (node (ref "C4") (pin "1") (pinfunction "1_1") (pintype "passive"))
      (node (ref "IC2") (pin "6") (pinfunction "-IN_6") (pintype "input"))
      (node (ref "IC3") (pin "12") (pinfunction "OUT_12") (pintype "output"))
    )
    (net (code "16") (name "Net-(IC2C--IN)") (class "Default")
      (node (ref "D1") (pin "A") (pinfunction "A_A") (pintype "passive"))
      (node (ref "IC2") (pin "9") (pinfunction "-IN_9") (pintype "input"))
      (node (ref "R1") (pin "2") (pinfunction "2_2") (pintype "passive"))
      (node (ref "R3") (pin "2") (pinfunction "2_2") (pintype "passive"))
      (node (ref "R4") (pin "2") (pinfunction "2_2") (pintype "passive"))
      (node (ref "R7") (pin "1") (pinfunction "1_1") (pintype "passive"))
    )
    (net (code "17") (name "Net-(IC2C-OUT)") (class "Default")
      (node (ref "D1") (pin "C") (pinfunction "C_C") (pintype "passive"))
      (node (ref "D3") (pin "A") (pinfunction "A_A") (pintype "passive"))
      (node (ref "IC2") (pin "8") (pinfunction "OUT_8") (pintype "output"))
    )
    (net (code "18") (name "Net-(IC2D--IN)") (class "Default")
      (node (ref "C3") (pin "1") (pinfunction "1_1") (pintype "passive"))
      (node (ref "IC2") (pin "13") (pinfunction "-IN_13") (pintype "input"))
      (node (ref "IC3") (pin "13") (pinfunction "OUT_13") (pintype "output"))
    )
    (net (code "19") (name "Net-(IC3A-IN)") (class "Default")
      (node (ref "IC3") (pin "2") (pinfunction "IN_2") (pintype "input"))
      (node (ref "R47") (pin "2") (pinfunction "2_2") (pintype "passive"))
      (node (ref "R49") (pin "2") (pinfunction "2_2") (pintype "passive"))
      (node (ref "R50") (pin "1") (pinfunction "1_1") (pintype "passive"))
    )
    (net (code "20") (name "Net-(IC3A-OUT)") (class "Default")
      (node (ref "C10") (pin "1") (pinfunction "1_1") (pintype "passive"))
      (node (ref "IC3") (pin "4") (pinfunction "OUT_4") (pintype "output"))
      (node (ref "IC5") (pin "6") (pinfunction "-IN_6") (pintype "input"))
    )
    (net (code "21") (name "Net-(IC3B-IN)") (class "Default")
      (node (ref "C7") (pin "1") (pinfunction "1_1") (pintype "passive"))
      (node (ref "IC3") (pin "7") (pinfunction "IN_7") (pintype "input"))
      (node (ref "R34") (pin "2") (pinfunction "2_2") (pintype "passive"))
      (node (ref "R37") (pin "2") (pinfunction "2_2") (pintype "passive"))
      (node (ref "R39") (pin "2") (pinfunction "2_2") (pintype "passive"))
    )
    (net (code "22") (name "Net-(IC3B-OUT)") (class "Default")
      (node (ref "C8") (pin "1") (pinfunction "1_1") (pintype "passive"))
      (node (ref "IC3") (pin "5") (pinfunction "OUT_5") (pintype "output"))
      (node (ref "IC6") (pin "6") (pinfunction "-IN_6") (pintype "input"))
    )
    (net (code "23") (name "Net-(IC3C-CTRL)") (class "Default")
      (node (ref "D4") (pin "C") (pinfunction "C_C") (pintype "passive"))
      (node (ref "IC3") (pin "11") (pinfunction "CTRL_11") (pintype "input"))
      (node (ref "R8") (pin "2") (pinfunction "2_2") (pintype "passive"))
    )
    (net (code "24") (name "Net-(IC3C-IN)") (class "Default")
      (node (ref "IC3") (pin "10") (pinfunction "IN_10") (pintype "input"))
      (node (ref "R10") (pin "2") (pinfunction "2_2") (pintype "passive"))
      (node (ref "R12") (pin "1") (pinfunction "1_1") (pintype "passive"))
    )
    (net (code "25") (name "Net-(IC3D-CTRL)") (class "Default")
      (node (ref "D3") (pin "C") (pinfunction "C_C") (pintype "passive"))
      (node (ref "IC3") (pin "14") (pinfunction "CTRL_14") (pintype "input"))
      (node (ref "R7") (pin "2") (pinfunction "2_2") (pintype "passive"))
    )
    (net (code "26") (name "Net-(IC3D-IN)") (class "Default")
      (node (ref "IC3") (pin "15") (pinfunction "IN_15") (pintype "input"))
      (node (ref "R11") (pin "1") (pinfunction "1_1") (pintype "passive"))
      (node (ref "R9") (pin "2") (pinfunction "2_2") (pintype "passive"))
    )
    (net (code "27") (name "Net-(IC4A-+IN)") (class "Default")
      (node (ref "IC4") (pin "3") (pinfunction "+IN_3") (pintype "input"))
      (node (ref "R14") (pin "2") (pinfunction "2_2") (pintype "passive"))
      (node (ref "R16") (pin "1") (pinfunction "1_1") (pintype "passive"))
    )
    (net (code "28") (name "Net-(IC4B-+IN)") (class "Default")
      (node (ref "IC4") (pin "5") (pinfunction "+IN_5") (pintype "input"))
      (node (ref "R13") (pin "2") (pinfunction "2_2") (pintype "passive"))
      (node (ref "R15") (pin "1") (pinfunction "1_1") (pintype "passive"))
    )
    (net (code "29") (name "Net-(IC5A-+IN)") (class "Default")
      (node (ref "C7") (pin "2") (pinfunction "2_2") (pintype "passive"))
      (node (ref "C8") (pin "2") (pinfunction "2_2") (pintype "passive"))
      (node (ref "IC5") (pin "3") (pinfunction "+IN_3") (pintype "input"))
      (node (ref "IC6") (pin "7") (pinfunction "OUT_7") (pintype "output"))
      (node (ref "R45") (pin "2") (pinfunction "2_2") (pintype "passive"))
      (node (ref "R47") (pin "1") (pinfunction "1_1") (pintype "passive"))
    )
    (net (code "30") (name "Net-(IC5A--IN)") (class "Default")
      (node (ref "IC5") (pin "2") (pinfunction "-IN_2") (pintype "input"))
      (node (ref "R44") (pin "2") (pinfunction "2_2") (pintype "passive"))
      (node (ref "R48") (pin "1") (pinfunction "1_1") (pintype "passive"))
    )
    (net (code "31") (name "Net-(IC5A-OUT)") (class "Default")
      (node (ref "IC5") (pin "1") (pinfunction "OUT_1") (pintype "output"))
      (node (ref "R48") (pin "2") (pinfunction "2_2") (pintype "passive"))
      (node (ref "R59") (pin "P$3") (pinfunction "A_P$3") (pintype "passive"))
    )
    (net (code "32") (name "Net-(IC5C-+IN)") (class "Default")
      (node (ref "IC5") (pin "10") (pinfunction "+IN_10") (pintype "input"))
      (node (ref "Q1") (pin "3") (pinfunction "C_3") (pintype "passive"))
      (node (ref "R20") (pin "1") (pinfunction "1_1") (pintype "passive"))
      (node (ref "R21") (pin "2") (pinfunction "2_2") (pintype "passive"))
    )
    (net (code "33") (name "Net-(IC5C--IN)") (class "Default")
      (node (ref "IC5") (pin "9") (pinfunction "-IN_9") (pintype "input"))
      (node (ref "R19") (pin "1") (pinfunction "1_1") (pintype "passive"))
      (node (ref "R22") (pin "2") (pinfunction "2_2") (pintype "passive"))
    )
    (net (code "34") (name "Net-(IC5D--IN)") (class "Default")
      (node (ref "IC5") (pin "13") (pinfunction "-IN_13") (pintype "input"))
      (node (ref "R23") (pin "1") (pinfunction "1_1") (pintype "passive"))
      (node (ref "R26") (pin "2") (pinfunction "2_2") (pintype "passive"))
      (node (ref "R29") (pin "2") (pinfunction "2_2") (pintype "passive"))
    )
    (net (code "35") (name "Net-(IC6A--IN)") (class "Default")
      (node (ref "IC6") (pin "2") (pinfunction "-IN_2") (pintype "input"))
      (node (ref "R30") (pin "2") (pinfunction "2_2") (pintype "passive"))
      (node (ref "R31") (pin "2") (pinfunction "2_2") (pintype "passive"))
      (node (ref "R32") (pin "1") (pinfunction "1_1") (pintype "passive"))
      (node (ref "R33") (pin "1") (pinfunction "1_1") (pintype "passive"))
    )
    (net (code "36") (name "Net-(IC6A-OUT)") (class "Default")
      (node (ref "IC6") (pin "1") (pinfunction "OUT_1") (pintype "output"))
      (node (ref "R33") (pin "2") (pinfunction "2_2") (pintype "passive"))
      (node (ref "R34") (pin "1") (pinfunction "1_1") (pintype "passive"))
    )
    (net (code "37") (name "Net-(IC6D--IN)") (class "Default")
      (node (ref "D5") (pin "A") (pinfunction "A_A") (pintype "passive"))
      (node (ref "IC6") (pin "13") (pinfunction "-IN_13") (pintype "input"))
      (node (ref "R41") (pin "2") (pinfunction "2_2") (pintype "passive"))
      (node (ref "R42") (pin "2") (pinfunction "2_2") (pintype "passive"))
      (node (ref "R43") (pin "2") (pinfunction "2_2") (pintype "passive"))
      (node (ref "R45") (pin "1") (pinfunction "1_1") (pintype "passive"))
      (node (ref "R46") (pin "1") (pinfunction "1_1") (pintype "passive"))
    )
    (net (code "38") (name "Net-(IC6D-OUT)") (class "Default")
      (node (ref "D5") (pin "C") (pinfunction "C_C") (pintype "passive"))
      (node (ref "D6") (pin "A") (pinfunction "A_A") (pintype "passive"))
      (node (ref "IC6") (pin "14") (pinfunction "OUT_14") (pintype "output"))
    )
    (net (code "39") (name "Net-(IC9A--IN)") (class "Default")
      (node (ref "C29") (pin "1") (pinfunction "1_1") (pintype "passive"))
      (node (ref "IC9") (pin "2") (pinfunction "-IN_2") (pintype "input"))
      (node (ref "R63") (pin "2") (pinfunction "2_2") (pintype "passive"))
      (node (ref "R64") (pin "1") (pinfunction "1_1") (pintype "passive"))
    )
    (net (code "40") (name "Net-(IC9A-OUT)") (class "Default")
      (node (ref "C29") (pin "2") (pinfunction "2_2") (pintype "passive"))
      (node (ref "IC9") (pin "1") (pinfunction "OUT_1") (pintype "output"))
      (node (ref "R62") (pin "1") (pinfunction "1_1") (pintype "passive"))
      (node (ref "R64") (pin "2") (pinfunction "2_2") (pintype "passive"))
    )
    (net (code "41") (name "Net-(IC9B--IN)") (class "Default")
      (node (ref "C32") (pin "1") (pinfunction "1_1") (pintype "passive"))
      (node (ref "IC9") (pin "6") (pinfunction "-IN_6") (pintype "input"))
      (node (ref "R65") (pin "1") (pinfunction "1_1") (pintype "passive"))
      (node (ref "R66") (pin "2") (pinfunction "2_2") (pintype "passive"))
    )
    (net (code "42") (name "Net-(IC9B-OUT)") (class "Default")
      (node (ref "C32") (pin "2") (pinfunction "2_2") (pintype "passive"))
      (node (ref "IC9") (pin "7") (pinfunction "OUT_7") (pintype "output"))
      (node (ref "R63") (pin "1") (pinfunction "1_1") (pintype "passive"))
      (node (ref "R65") (pin "2") (pinfunction "2_2") (pintype "passive"))
    )
    (net (code "43") (name "Net-(J1-3)") (class "Default")
      (node (ref "J1") (pin "P3") (pinfunction "3_P3") (pintype "passive"))
      (node (ref "R51") (pin "P$1") (pinfunction "E_P$1") (pintype "passive"))
    )
    (net (code "44") (name "Net-(J2-3)") (class "Default")
      (node (ref "J2") (pin "P3") (pinfunction "3_P3") (pintype "passive"))
      (node (ref "R52") (pin "P$1") (pinfunction "E_P$1") (pintype "passive"))
    )
    (net (code "45") (name "Net-(J3-3)") (class "Default")
      (node (ref "C5") (pin "1") (pinfunction "1_1") (pintype "passive"))
      (node (ref "J3") (pin "P3") (pinfunction "3_P3") (pintype "passive"))
    )
    (net (code "46") (name "Net-(J4-3)") (class "Default")
      (node (ref "J4") (pin "P3") (pinfunction "3_P3") (pintype "passive"))
      (node (ref "R53") (pin "P$1") (pinfunction "E_P$1") (pintype "passive"))
    )
    (net (code "47") (name "Net-(Q1-B)") (class "Default")
      (node (ref "Q1") (pin "1") (pinfunction "B_1") (pintype "passive"))
      (node (ref "R17") (pin "2") (pinfunction "2_2") (pintype "passive"))
      (node (ref "SW1") (pin "P$2") (pinfunction "P$2_P$2") (pintype "passive"))
    )
    (net (code "48") (name "Net-(R18-Pad2)") (class "Default")
      (node (ref "R18") (pin "2") (pinfunction "2_2") (pintype "passive"))
      (node (ref "SW1") (pin "P$1") (pinfunction "P$1_P$1") (pintype "passive"))
    )
    (net (code "49") (name "Net-(R24-Pad1)") (class "Default")
      (node (ref "R24") (pin "1") (pinfunction "1_1") (pintype "passive"))
      (node (ref "R26") (pin "1") (pinfunction "1_1") (pintype "passive"))
      (node (ref "R27") (pin "2") (pinfunction "2_2") (pintype "passive"))
    )
    (net (code "50") (name "Net-(R25-Pad1)") (class "Default")
      (node (ref "R25") (pin "1") (pinfunction "1_1") (pintype "passive"))
      (node (ref "R27") (pin "1") (pinfunction "1_1") (pintype "passive"))
      (node (ref "R28") (pin "2") (pinfunction "2_2") (pintype "passive"))
    )
    (net (code "51") (name "Net-(R31-Pad1)") (class "Default")
      (node (ref "R31") (pin "1") (pinfunction "1_1") (pintype "passive"))
      (node (ref "R35") (pin "2") (pinfunction "2_2") (pintype "passive"))
      (node (ref "R36") (pin "2") (pinfunction "2_2") (pintype "passive"))
      (node (ref "R38") (pin "2") (pinfunction "2_2") (pintype "passive"))
      (node (ref "R44") (pin "1") (pinfunction "1_1") (pintype "passive"))
    )
    (net (code "52") (name "Net-(R51-S)") (class "Default")
      (node (ref "R1") (pin "1") (pinfunction "1_1") (pintype "passive"))
      (node (ref "R51") (pin "P$2") (pinfunction "S_P$2") (pintype "passive"))
    )
    (net (code "53") (name "Net-(R52-S)") (class "Default")
      (node (ref "R2") (pin "1") (pinfunction "1_1") (pintype "passive"))
      (node (ref "R52") (pin "P$2") (pinfunction "S_P$2") (pintype "passive"))
    )
    (net (code "54") (name "Net-(R53-S)") (class "Default")
      (node (ref "R41") (pin "1") (pinfunction "1_1") (pintype "passive"))
      (node (ref "R53") (pin "P$2") (pinfunction "S_P$2") (pintype "passive"))
    )
    (net (code "55") (name "Net-(R54-S)") (class "Default")
      (node (ref "R3") (pin "1") (pinfunction "1_1") (pintype "passive"))
      (node (ref "R54") (pin "P$2") (pinfunction "S_P$2") (pintype "passive"))
    )
    (net (code "56") (name "Net-(R55-S)") (class "Default")
      (node (ref "R4") (pin "1") (pinfunction "1_1") (pintype "passive"))
      (node (ref "R55") (pin "P$2") (pinfunction "S_P$2") (pintype "passive"))
    )
    (net (code "57") (name "Net-(R56-S)") (class "Default")
      (node (ref "R5") (pin "1") (pinfunction "1_1") (pintype "passive"))
      (node (ref "R56") (pin "P$2") (pinfunction "S_P$2") (pintype "passive"))
    )
    (net (code "58") (name "Net-(R57-S)") (class "Default")
      (node (ref "R57") (pin "P$2") (pinfunction "S_P$2") (pintype "passive"))
      (node (ref "R6") (pin "1") (pinfunction "1_1") (pintype "passive"))
    )
    (net (code "59") (name "Net-(R58-S)") (class "Default")
      (node (ref "R43") (pin "1") (pinfunction "1_1") (pintype "passive"))
      (node (ref "R58") (pin "P$2") (pinfunction "S_P$2") (pintype "passive"))
    )
    (net (code "60") (name "Net-(R59-S)") (class "Default")
      (node (ref "R39") (pin "1") (pinfunction "1_1") (pintype "passive"))
      (node (ref "R40") (pin "2") (pinfunction "2_2") (pintype "passive"))
      (node (ref "R59") (pin "P$2") (pinfunction "S_P$2") (pintype "passive"))
    )
    (net (code "61") (name "Net-(R60-S)") (class "Default")
      (node (ref "R18") (pin "1") (pinfunction "1_1") (pintype "passive"))
      (node (ref "R60") (pin "P$2") (pinfunction "S_P$2") (pintype "passive"))
    )
    (net (code "62") (name "Net-(R61-S)") (class "Default")
      (node (ref "R42") (pin "1") (pinfunction "1_1") (pintype "passive"))
      (node (ref "R61") (pin "P$2") (pinfunction "S_P$2") (pintype "passive"))
    )
    (net (code "63") (name "OUT") (class "Default")
      (node (ref "C10") (pin "2") (pinfunction "2_2") (pintype "passive"))
      (node (ref "IC5") (pin "7") (pinfunction "OUT_7") (pintype "output"))
      (node (ref "R32") (pin "2") (pinfunction "2_2") (pintype "passive"))
      (node (ref "R50") (pin "2") (pinfunction "2_2") (pintype "passive"))
      (node (ref "R66") (pin "1") (pinfunction "1_1") (pintype "passive"))
    )
    (net (code "64") (name "OUT_AMP") (class "Default")
      (node (ref "J9") (pin "P3") (pinfunction "3_P3") (pintype "passive"))
      (node (ref "R62") (pin "2") (pinfunction "2_2") (pintype "passive"))
    )
    (net (code "65") (name "P1") (class "Default")
      (node (ref "IC4") (pin "7") (pinfunction "OUT_7") (pintype "output"))
      (node (ref "J8") (pin "P3") (pinfunction "3_P3") (pintype "passive"))
      (node (ref "R11") (pin "2") (pinfunction "2_2") (pintype "passive"))
      (node (ref "R15") (pin "2") (pinfunction "2_2") (pintype "passive"))
      (node (ref "R17") (pin "1") (pinfunction "1_1") (pintype "passive"))
    )
    (net (code "66") (name "P2") (class "Default")
      (node (ref "IC1") (pin "10") (pinfunction "CLK_10") (pintype "input"))
      (node (ref "IC4") (pin "1") (pinfunction "OUT_1") (pintype "output"))
      (node (ref "J5") (pin "P3") (pinfunction "3_P3") (pintype "passive"))
      (node (ref "R12") (pin "2") (pinfunction "2_2") (pintype "passive"))
      (node (ref "R16") (pin "2") (pinfunction "2_2") (pintype "passive"))
    )
    (net (code "67") (name "PWM") (class "Default")
      (node (ref "IC6") (pin "8") (pinfunction "OUT_8") (pintype "output"))
      (node (ref "J10") (pin "P3") (pinfunction "3_P3") (pintype "passive"))
      (node (ref "R36") (pin "1") (pinfunction "1_1") (pintype "passive"))
    )
    (net (code "68") (name "RUN_CV") (class "Default")
      (node (ref "IC5") (pin "14") (pinfunction "OUT_14") (pintype "output"))
      (node (ref "J11") (pin "P3") (pinfunction "3_P3") (pintype "passive"))
      (node (ref "R29") (pin "1") (pinfunction "1_1") (pintype "passive"))
      (node (ref "R35") (pin "1") (pinfunction "1_1") (pintype "passive"))
      (node (ref "R55") (pin "P$1") (pinfunction "E_P$1") (pintype "passive"))
      (node (ref "R57") (pin "P$1") (pinfunction "E_P$1") (pintype "passive"))
      (node (ref "R61") (pin "P$1") (pinfunction "E_P$1") (pintype "passive"))
    )
    (net (code "69") (name "T1") (class "Default")
      (node (ref "C3") (pin "2") (pinfunction "2_2") (pintype "passive"))
      (node (ref "IC2") (pin "14") (pinfunction "OUT_14") (pintype "output"))
      (node (ref "IC6") (pin "9") (pinfunction "-IN_9") (pintype "input"))
      (node (ref "J2") (pin "P2") (pinfunction "2_P2") (pintype "passive"))
      (node (ref "J6") (pin "P3") (pinfunction "3_P3") (pintype "passive"))
      (node (ref "R13") (pin "1") (pinfunction "1_1") (pintype "passive"))
    )
    (net (code "70") (name "T2") (class "Default")
      (node (ref "C4") (pin "2") (pinfunction "2_2") (pintype "passive"))
      (node (ref "IC2") (pin "7") (pinfunction "OUT_7") (pintype "output"))
      (node (ref "IC6") (pin "10") (pinfunction "+IN_10") (pintype "input"))
      (node (ref "J1") (pin "P2") (pinfunction "2_P2") (pintype "passive"))
      (node (ref "J4") (pin "P2") (pinfunction "2_P2") (pintype "passive"))
      (node (ref "J7") (pin "P3") (pinfunction "3_P3") (pintype "passive"))
      (node (ref "R14") (pin "1") (pinfunction "1_1") (pintype "passive"))
    )
    (net (code "71") (name "V+") (class "Default")
      (node (ref "C13") (pin "1") (pinfunction "1_1") (pintype "passive"))
      (node (ref "C15") (pin "+") (pinfunction "+_+") (pintype "passive"))
      (node (ref "C17") (pin "1") (pinfunction "1_1") (pintype "passive"))
      (node (ref "C19") (pin "1") (pinfunction "1_1") (pintype "passive"))
      (node (ref "C21") (pin "1") (pinfunction "1_1") (pintype "passive"))
      (node (ref "C23") (pin "1") (pinfunction "1_1") (pintype "passive"))
      (node (ref "C25") (pin "1") (pinfunction "1_1") (pintype "passive"))
      (node (ref "C27") (pin "1") (pinfunction "1_1") (pintype "passive"))
      (node (ref "C30") (pin "1") (pinfunction "1_1") (pintype "passive"))
      (node (ref "D7") (pin "2") (pinfunction "-_2") (pintype "passive"))
      (node (ref "D8") (pin "1") (pinfunction "+_1") (pintype "passive"))
      (node (ref "IC1") (pin "16") (pinfunction "VDD_16") (pintype "power_in"))
      (node (ref "IC2") (pin "4") (pinfunction "V+_4") (pintype "power_in"))
      (node (ref "IC3") (pin "16") (pinfunction "V+_16") (pintype "power_in"))
      (node (ref "IC4") (pin "8") (pinfunction "V+_8") (pintype "power_in"))
      (node (ref "IC5") (pin "4") (pinfunction "V+_4") (pintype "power_in"))
      (node (ref "IC6") (pin "4") (pinfunction "V+_4") (pintype "power_in"))
      (node (ref "IC7") (pin "OUT") (pinfunction "OUT_OUT") (pintype "passive"))
      (node (ref "IC9") (pin "8") (pinfunction "V+_8") (pintype "power_in"))
      (node (ref "R60") (pin "P$1") (pinfunction "E_P$1") (pintype "passive"))
    )
    (net (code "72") (name "V-") (class "Default")
      (node (ref "C14") (pin "2") (pinfunction "2_2") (pintype "passive"))
      (node (ref "C16") (pin "-") (pinfunction "-_-") (pintype "passive"))
      (node (ref "C18") (pin "2") (pinfunction "2_2") (pintype "passive"))
      (node (ref "C20") (pin "2") (pinfunction "2_2") (pintype "passive"))
      (node (ref "C22") (pin "2") (pinfunction "2_2") (pintype "passive"))
      (node (ref "C24") (pin "2") (pinfunction "2_2") (pintype "passive"))
      (node (ref "C26") (pin "2") (pinfunction "2_2") (pintype "passive"))
      (node (ref "C28") (pin "2") (pinfunction "2_2") (pintype "passive"))
      (node (ref "C31") (pin "2") (pinfunction "2_2") (pintype "passive"))
      (node (ref "D10") (pin "1") (pinfunction "+_1") (pintype "passive"))
      (node (ref "D11") (pin "A") (pinfunction "A_A") (pintype "passive"))
      (node (ref "D9") (pin "2") (pinfunction "-_2") (pintype "passive"))
      (node (ref "IC1") (pin "8") (pinfunction "VSS_8") (pintype "power_in"))
      (node (ref "IC1") (pin "9") (pinfunction "P/~{S}_9") (pintype "input"))
      (node (ref "IC2") (pin "11") (pinfunction "V-_11") (pintype "power_in"))
      (node (ref "IC3") (pin "9") (pinfunction "V-_9") (pintype "power_in"))
      (node (ref "IC4") (pin "4") (pinfunction "V-_4") (pintype "power_in"))
      (node (ref "IC5") (pin "11") (pinfunction "V-_11") (pintype "power_in"))
      (node (ref "IC6") (pin "11") (pinfunction "V-_11") (pintype "power_in"))
      (node (ref "IC8") (pin "OUT") (pinfunction "OUT_OUT") (pintype "passive"))
      (node (ref "IC9") (pin "4") (pinfunction "V-_4") (pintype "power_in"))
      (node (ref "R54") (pin "P$3") (pinfunction "A_P$3") (pintype "passive"))
      (node (ref "R56") (pin "P$3") (pinfunction "A_P$3") (pintype "passive"))
      (node (ref "R58") (pin "P$3") (pinfunction "A_P$3") (pintype "passive"))
      (node (ref "R60") (pin "P$3") (pinfunction "A_P$3") (pintype "passive"))
    )
    (net (code "73") (name "VCC") (class "Default")
      (node (ref "C100") (pin "+") (pinfunction "+_+") (pintype "passive"))
      (node (ref "C11") (pin "1") (pinfunction "1_1") (pintype "passive"))
      (node (ref "D100") (pin "C") (pinfunction "C_C") (pintype "passive"))
      (node (ref "D8") (pin "2") (pinfunction "-_2") (pintype "passive"))
      (node (ref "IC7") (pin "IN") (pinfunction "IN_IN") (pintype "input"))
    )
    (net (code "74") (name "VEE") (class "Default")
      (node (ref "C12") (pin "2") (pinfunction "2_2") (pintype "passive"))
      (node (ref "C200") (pin "-") (pinfunction "-_-") (pintype "passive"))
      (node (ref "D200") (pin "A") (pinfunction "A_A") (pintype "passive"))
      (node (ref "D9") (pin "1") (pinfunction "+_1") (pintype "passive"))
      (node (ref "IC8") (pin "IN") (pinfunction "IN_IN") (pintype "input"))
    )
    (net (code "75") (name "XOR") (class "Default")
      (node (ref "IC1") (pin "11") (pinfunction "SI_11") (pintype "input"))
      (node (ref "IC5") (pin "8") (pinfunction "OUT_8") (pintype "output"))
      (node (ref "J12") (pin "P3") (pinfunction "3_P3") (pintype "passive"))
      (node (ref "R22") (pin "1") (pinfunction "1_1") (pintype "passive"))
    )
    (net (code "76") (name "unconnected-(IC1A-P1-Pad7)") (class "Default")
      (node (ref "IC1") (pin "7") (pinfunction "P1_7") (pintype "input"))
    )
    (net (code "77") (name "unconnected-(IC1A-P2-Pad6)") (class "Default")
      (node (ref "IC1") (pin "6") (pinfunction "P2_6") (pintype "input"))
    )
    (net (code "78") (name "unconnected-(IC1A-P3-Pad5)") (class "Default")
      (node (ref "IC1") (pin "5") (pinfunction "P3_5") (pintype "input"))
    )
    (net (code "79") (name "unconnected-(IC1A-P4-Pad4)") (class "Default")
      (node (ref "IC1") (pin "4") (pinfunction "P4_4") (pintype "input"))
    )
    (net (code "80") (name "unconnected-(IC1A-P5-Pad13)") (class "Default")
      (node (ref "IC1") (pin "13") (pinfunction "P5_13") (pintype "input"))
    )
    (net (code "81") (name "unconnected-(IC1A-P6-Pad14)") (class "Default")
      (node (ref "IC1") (pin "14") (pinfunction "P6_14") (pintype "input"))
    )
    (net (code "82") (name "unconnected-(IC1A-P7-Pad15)") (class "Default")
      (node (ref "IC1") (pin "15") (pinfunction "P7_15") (pintype "input"))
    )
    (net (code "83") (name "unconnected-(IC1A-P8-Pad1)") (class "Default")
      (node (ref "IC1") (pin "1") (pinfunction "P8_1") (pintype "input"))
    )
    (net (code "84") (name "unconnected-(IC3E-MODE-Pad1)") (class "Default")
      (node (ref "IC3") (pin "1") (pinfunction "MODE_1") (pintype "input"))
    )
    (net (code "85") (name "unconnected-(J3-2-PadP2)") (class "Default")
      (node (ref "J3") (pin "P2") (pinfunction "2_P2") (pintype "passive"))
    )
    (net (code "86") (name "unconnected-(J5-2-PadP2)") (class "Default")
      (node (ref "J5") (pin "P2") (pinfunction "2_P2") (pintype "passive"))
    )
    (net (code "87") (name "unconnected-(J6-2-PadP2)") (class "Default")
      (node (ref "J6") (pin "P2") (pinfunction "2_P2") (pintype "passive"))
    )
    (net (code "88") (name "unconnected-(J7-2-PadP2)") (class "Default")
      (node (ref "J7") (pin "P2") (pinfunction "2_P2") (pintype "passive"))
    )
    (net (code "89") (name "unconnected-(J8-2-PadP2)") (class "Default")
      (node (ref "J8") (pin "P2") (pinfunction "2_P2") (pintype "passive"))
    )
    (net (code "90") (name "unconnected-(J9-2-PadP2)") (class "Default")
      (node (ref "J9") (pin "P2") (pinfunction "2_P2") (pintype "passive"))
    )
    (net (code "91") (name "unconnected-(J10-2-PadP2)") (class "Default")
      (node (ref "J10") (pin "P2") (pinfunction "2_P2") (pintype "passive"))
    )
    (net (code "92") (name "unconnected-(J11-2-PadP2)") (class "Default")
      (node (ref "J11") (pin "P2") (pinfunction "2_P2") (pintype "passive"))
    )
    (net (code "93") (name "unconnected-(J12-2-PadP2)") (class "Default")
      (node (ref "J12") (pin "P2") (pinfunction "2_P2") (pintype "passive"))
    )
    (net (code "94") (name "unconnected-(SW1-PadP$3)") (class "Default")
      (node (ref "SW1") (pin "P$3") (pinfunction "P$3_P$3") (pintype "passive"))
    )
  )
)
